# Sheet_1_2024-11-29.net
KiCad netlist of a schematic drawn in Altium Designer
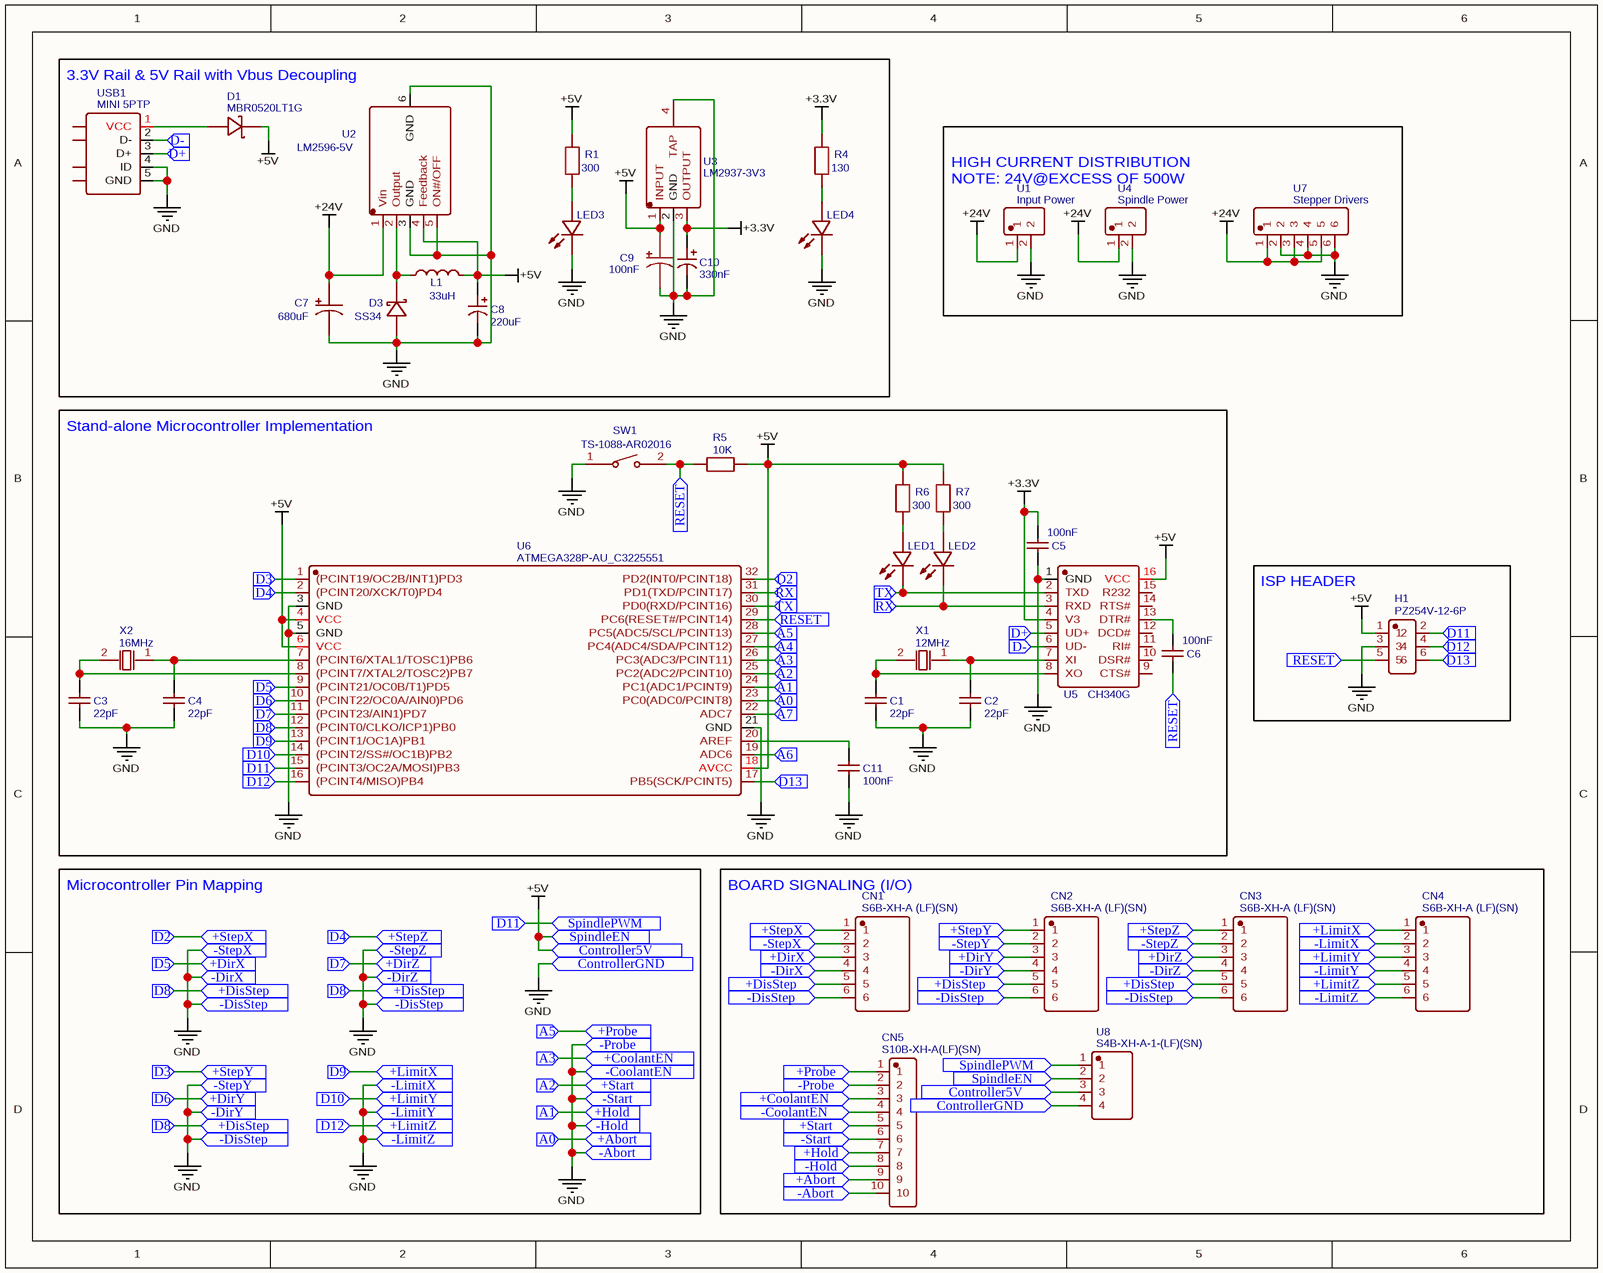
[diagram p0: Sheet_1_2024-11-29.schdoc]

(export (version "E")
  (design (tool "Eeschema 10.0.6"))
  (components
    (comp (ref "C1")
      (value "22pF")
      (fields (field (name "MANUFACTURER") "YAGEO(国巨)"))
      (libsource (lib "altium-import") (part "root_1_22pF_"))
    )
    (comp (ref "C2")
      (value "22pF")
      (fields (field (name "MANUFACTURER") "YAGEO(国巨)"))
      (libsource (lib "altium-import") (part "root_1_22pF_"))
    )
    (comp (ref "C3")
      (value "22pF")
      (fields (field (name "MANUFACTURER") "YAGEO(国巨)"))
      (libsource (lib "altium-import") (part "root_1_22pF_"))
    )
    (comp (ref "C4")
      (value "22pF")
      (fields (field (name "MANUFACTURER") "YAGEO(国巨)"))
      (libsource (lib "altium-import") (part "root_1_22pF_"))
    )
    (comp (ref "C5")
      (value "100nF")
      (fields (field (name "MANUFACTURER") "YAGEO(国巨)"))
      (libsource (lib "altium-import") (part "root_3_100nF_"))
    )
    (comp (ref "C6")
      (value "100nF")
      (fields (field (name "MANUFACTURER") "YAGEO(国巨)"))
      (libsource (lib "altium-import") (part "root_3_100nF_"))
    )
    (comp (ref "C7")
      (value "680uF")
      (fields (field (name "MANUFACTURER") "lelon(立隆)") (field (name "CONTRIBUTOR") "LCSC"))
      (libsource (lib "altium-import") (part "root_3_680uF_"))
    )
    (comp (ref "C8")
      (value "220uF")
      (fields (field (name "MANUFACTURER") "KNSCHA(科尼盛)") (field (name "CONTRIBUTOR") "lcsc"))
      (libsource (lib "altium-import") (part "root_3_220uF_"))
    )
    (comp (ref "C9")
      (value "100nF")
      (fields
        (field (name "MANUFACTURER") "HUAWEI(华威集团)")
        (field (name "MANUFACTURER PART") "VT1H0R1MB054000CE0")
        (field (name "CONTRIBUTOR") "LCSC")
      )
      (libsource (lib "altium-import") (part "root_0_100nF_"))
    )
    (comp (ref "C10")
      (value "330nF")
      (fields
        (field (name "MANUFACTURER") "ST(先科)")
        (field (name "MANUFACTURER PART") "CK1HR33MCRC54")
        (field (name "CONTRIBUTOR") "LCSC")
      )
      (libsource (lib "altium-import") (part "root_3_330nF_"))
    )
    (comp (ref "C11")
      (value "100nF")
      (fields (field (name "MANUFACTURER") "YAGEO(国巨)"))
      (libsource (lib "altium-import") (part "root_1_100nF_"))
    )
    (comp (ref "CN1")
      (value "S6B-XH-A (LF)(SN)")
      (fields (field (name "MANUFACTURER") "JST") (field (name "CONTRIBUTOR") "LCSC"))
      (libsource (lib "altium-import") (part "root_0_S6B-XH-A (LF)(SN)_"))
    )
    (comp (ref "CN2")
      (value "S6B-XH-A (LF)(SN)")
      (fields (field (name "MANUFACTURER") "JST") (field (name "CONTRIBUTOR") "LCSC"))
      (libsource (lib "altium-import") (part "root_0_S6B-XH-A (LF)(SN)_"))
    )
    (comp (ref "CN3")
      (value "S6B-XH-A (LF)(SN)")
      (fields (field (name "MANUFACTURER") "JST") (field (name "CONTRIBUTOR") "LCSC"))
      (libsource (lib "altium-import") (part "root_0_S6B-XH-A (LF)(SN)_"))
    )
    (comp (ref "CN4")
      (value "S6B-XH-A (LF)(SN)")
      (fields (field (name "MANUFACTURER") "JST") (field (name "CONTRIBUTOR") "LCSC"))
      (libsource (lib "altium-import") (part "root_0_S6B-XH-A (LF)(SN)_"))
    )
    (comp (ref "CN5")
      (value "S10B-XH-A(LF)(SN)")
      (fields (field (name "MANUFACTURER") "JST") (field (name "CONTRIBUTOR") "LCSC"))
      (libsource (lib "altium-import") (part "root_0_S10B-XH-A(LF)(SN)_"))
    )
    (comp (ref "D1")
      (value "MBR0520LT1G")
      (fields (field (name "MANUFACTURER") "onsemi(安森美)"))
      (libsource (lib "altium-import") (part "root_2_MBR0520LT1G_"))
    )
    (comp (ref "D3")
      (value "SS34")
      (fields (field (name "MANUFACTURER") "DOWO(东沃)") (field (name "CONTRIBUTOR") "lcsc"))
      (libsource (lib "altium-import") (part "root_3_SS34_"))
    )
    (comp (ref "H1")
      (value "PZ254V-12-6P")
      (fields (field (name "MANUFACTURER") "XFCN(兴飞)") (field (name "CONTRIBUTOR") "LCSC"))
      (libsource (lib "altium-import") (part "root_0_PZ254V-12-6P_"))
    )
    (comp (ref "L1")
      (value "33uH")
      (fields (field (name "MANUFACTURER") "GLE(格莱尔)") (field (name "CONTRIBUTOR") "lcsc"))
      (libsource (lib "altium-import") (part "root_0_33uH_"))
    )
    (comp (ref "LED1")
      (value "SZYY0603O")
      (fields (field (name "MANUFACTURER") "yongyu(永裕光电)") (field (name "CONTRIBUTOR") "LCSC"))
      (libsource (lib "altium-import") (part "root_1_SZYY0603O_"))
    )
    (comp (ref "LED2")
      (value "SZYY0603O")
      (fields (field (name "MANUFACTURER") "yongyu(永裕光电)") (field (name "CONTRIBUTOR") "LCSC"))
      (libsource (lib "altium-import") (part "root_1_SZYY0603O_"))
    )
    (comp (ref "LED3")
      (value "SZYY0603O")
      (fields (field (name "MANUFACTURER") "yongyu(永裕光电)") (field (name "CONTRIBUTOR") "LCSC"))
      (libsource (lib "altium-import") (part "root_1_SZYY0603O_"))
    )
    (comp (ref "LED4")
      (value "SZYY0603O")
      (fields (field (name "MANUFACTURER") "yongyu(永裕光电)") (field (name "CONTRIBUTOR") "LCSC"))
      (libsource (lib "altium-import") (part "root_1_SZYY0603O_"))
    )
    (comp (ref "R1")
      (value "300")
      (fields (field (name "MANUFACTURER") "Milliohm(毫欧)") (field (name "CONTRIBUTOR") "lcsc"))
      (libsource (lib "altium-import") (part "root_1_300_"))
    )
    (comp (ref "R4")
      (value "130")
      (fields (field (name "MANUFACTURER") "Milliohm(毫欧)") (field (name "CONTRIBUTOR") "lcsc"))
      (libsource (lib "altium-import") (part "root_1_130_"))
    )
    (comp (ref "R5")
      (value "10K")
      (fields (field (name "MANUFACTURER") "Milliohm(毫欧)") (field (name "CONTRIBUTOR") "lcsc"))
      (libsource (lib "altium-import") (part "root_2_10K_"))
    )
    (comp (ref "R6")
      (value "300")
      (fields (field (name "MANUFACTURER") "Milliohm(毫欧)") (field (name "CONTRIBUTOR") "lcsc"))
      (libsource (lib "altium-import") (part "root_1_300_"))
    )
    (comp (ref "R7")
      (value "300")
      (fields (field (name "MANUFACTURER") "Milliohm(毫欧)") (field (name "CONTRIBUTOR") "lcsc"))
      (libsource (lib "altium-import") (part "root_1_300_"))
    )
    (comp (ref "SW1")
      (value "TS-1088-AR02016")
      (fields (field (name "MANUFACTURER") "XUNPU(讯普)") (field (name "CONTRIBUTOR") "LCSC"))
      (libsource (lib "altium-import") (part "root_0_TS-1088-AR02016_"))
    )
    (comp (ref "U1")
      (value "Input Power")
      (fields (field (name "MANUFACTURER") "DORABO(地博电气)") (field (name "CONTRIBUTOR") "LCSC"))
      (libsource (lib "altium-import") (part "root_1_Input Power_"))
    )
    (comp (ref "U2")
      (value "LM2596-5V")
      (fields (field (name "MANUFACTURER") "MSKSEMI(美森科)") (field (name "CONTRIBUTOR") "lcsc"))
      (libsource (lib "altium-import") (part "root_1_LM2596-5V_"))
    )
    (comp (ref "U3")
      (value "LM2937-3V3")
      (fields (field (name "MANUFACTURER") "TI(德州仪器)") (field (name "CONTRIBUTOR") "LCSC"))
      (libsource (lib "altium-import") (part "root_0_LM2937-3V3_"))
    )
    (comp (ref "U4")
      (value "Spindle Power")
      (fields (field (name "MANUFACTURER") "DORABO(地博电气)") (field (name "CONTRIBUTOR") "LCSC"))
      (libsource (lib "altium-import") (part "root_1_Spindle Power_"))
    )
    (comp (ref "U5")
      (value "CH340G")
      (fields (field (name "MANUFACTURER") "WCH(南京沁恒)"))
      (libsource (lib "altium-import") (part "root_0_CH340G_"))
    )
    (comp (ref "U6")
      (value "ATMEGA328P-AU_C3225551")
      (fields (field (name "MANUFACTURER") "MICROCHIP(美国微芯)") (field (name "CONTRIBUTOR") "lcsc"))
      (libsource (lib "altium-import") (part "root_0_ATMEGA328P-AU_C3225551_"))
    )
    (comp (ref "U7")
      (value "Stepper Drivers")
      (fields (field (name "MANUFACTURER") "DORABO(地博电气)") (field (name "CONTRIBUTOR") "LCSC"))
      (libsource (lib "altium-import") (part "root_1_Stepper Drivers_"))
    )
    (comp (ref "U8")
      (value "S4B-XH-A-1-(LF)(SN)")
      (fields (field (name "MANUFACTURER") "JST") (field (name "CONTRIBUTOR") "LCSC"))
      (libsource (lib "altium-import") (part "root_0_S4B-XH-A-1-(LF)(SN)_"))
    )
    (comp (ref "USB1")
      (value "MINI 5PTP")
      (fields (field (name "MANUFACTURER") "SHOU HAN(首韩)") (field (name "CONTRIBUTOR") "LCSC"))
      (libsource (lib "altium-import") (part "root_0_MINI 5PTP_"))
    )
    (comp (ref "X1")
      (value "12MHz")
      (fields (field (name "MANUFACTURER") "ECS") (field (name "CONTRIBUTOR") "lcsc"))
      (libsource (lib "altium-import") (part "root_2_12MHz_"))
    )
    (comp (ref "X2")
      (value "16MHz")
      (fields (field (name "MANUFACTURER") "ECS") (field (name "CONTRIBUTOR") "lcsc"))
      (libsource (lib "altium-import") (part "root_2_16MHz_"))
    )
  )
  (nets
    (net (code "1") (name "+3.3V") (class "Default")
      (node (ref "C10") (pin "1") (pinfunction "1_1") (pintype "passive"))
      (node (ref "C5") (pin "1") (pinfunction "1_1") (pintype "passive"))
      (node (ref "R4") (pin "2") (pinfunction "2_2") (pintype "passive"))
      (node (ref "U3") (pin "3") (pinfunction "OUTPUT_3") (pintype "passive"))
      (node (ref "U5") (pin "4") (pinfunction "V3_4") (pintype "passive"))
    )
    (net (code "2") (name "+5V") (class "Default")
      (node (ref "C8") (pin "1") (pinfunction "1_1") (pintype "passive"))
      (node (ref "C9") (pin "1") (pinfunction "1_1") (pintype "passive"))
      (node (ref "D1") (pin "1") (pinfunction "C_1") (pintype "passive"))
      (node (ref "H1") (pin "1") (pinfunction "1_1") (pintype "passive"))
      (node (ref "L1") (pin "2") (pinfunction "2_2") (pintype "passive"))
      (node (ref "R1") (pin "2") (pinfunction "2_2") (pintype "passive"))
      (node (ref "R5") (pin "1") (pinfunction "1_1") (pintype "passive"))
      (node (ref "R6") (pin "2") (pinfunction "2_2") (pintype "passive"))
      (node (ref "R7") (pin "2") (pinfunction "2_2") (pintype "passive"))
      (node (ref "U2") (pin "4") (pinfunction "Feedback_4") (pintype "passive"))
      (node (ref "U3") (pin "1") (pinfunction "INPUT_1") (pintype "passive"))
      (node (ref "U5") (pin "16") (pinfunction "VCC_16") (pintype "passive"))
      (node (ref "U6") (pin "18") (pinfunction "AVCC_18") (pintype "passive"))
      (node (ref "U6") (pin "4") (pinfunction "VCC_4") (pintype "passive"))
      (node (ref "U6") (pin "6") (pinfunction "VCC_6") (pintype "passive"))
      (node (ref "U8") (pin "2") (pinfunction "2_2") (pintype "passive"))
      (node (ref "U8") (pin "3") (pinfunction "3_3") (pintype "passive"))
    )
    (net (code "3") (name "+24V") (class "Default")
      (node (ref "C7") (pin "1") (pinfunction "1_1") (pintype "passive"))
      (node (ref "U1") (pin "1") (pinfunction "1_1") (pintype "passive"))
      (node (ref "U2") (pin "1") (pinfunction "Vin_1") (pintype "passive"))
      (node (ref "U4") (pin "1") (pinfunction "1_1") (pintype "passive"))
      (node (ref "U7") (pin "1") (pinfunction "1_1") (pintype "passive"))
      (node (ref "U7") (pin "3") (pinfunction "3_3") (pintype "passive"))
      (node (ref "U7") (pin "5") (pinfunction "5_5") (pintype "passive"))
    )
    (net (code "4") (name "/+Abort") (class "Default")
      (node (ref "CN5") (pin "9") (pinfunction "9_9") (pintype "passive"))
      (node (ref "U6") (pin "23") (pinfunction "PC0(ADC0/PCINT8)_23") (pintype "passive"))
    )
    (net (code "5") (name "/+CoolantEN") (class "Default")
      (node (ref "CN5") (pin "3") (pinfunction "3_3") (pintype "passive"))
      (node (ref "U6") (pin "26") (pinfunction "PC3(ADC3/PCINT11)_26") (pintype "passive"))
    )
    (net (code "6") (name "/+DirX") (class "Default")
      (node (ref "CN1") (pin "3") (pinfunction "3_3") (pintype "passive"))
      (node (ref "U6") (pin "9") (pinfunction "(PCINT21/OC0B/T1)PD5_9") (pintype "passive"))
    )
    (net (code "7") (name "/+DirY") (class "Default")
      (node (ref "CN2") (pin "3") (pinfunction "3_3") (pintype "passive"))
      (node (ref "U6") (pin "10") (pinfunction "(PCINT22/OC0A/AIN0)PD6_10") (pintype "passive"))
    )
    (net (code "8") (name "/+DirZ") (class "Default")
      (node (ref "CN3") (pin "3") (pinfunction "3_3") (pintype "passive"))
      (node (ref "U6") (pin "11") (pinfunction "(PCINT23/AIN1)PD7_11") (pintype "passive"))
    )
    (net (code "9") (name "/+DisStep") (class "Default")
      (node (ref "CN1") (pin "5") (pinfunction "5_5") (pintype "passive"))
      (node (ref "CN2") (pin "5") (pinfunction "5_5") (pintype "passive"))
      (node (ref "CN3") (pin "5") (pinfunction "5_5") (pintype "passive"))
      (node (ref "U6") (pin "12") (pinfunction "(PCINT0/CLKO/ICP1)PB0_12") (pintype "passive"))
    )
    (net (code "10") (name "/+Hold") (class "Default")
      (node (ref "CN5") (pin "7") (pinfunction "7_7") (pintype "passive"))
      (node (ref "U6") (pin "24") (pinfunction "PC1(ADC1/PCINT9)_24") (pintype "passive"))
    )
    (net (code "11") (name "/+LimitX") (class "Default")
      (node (ref "CN4") (pin "1") (pinfunction "1_1") (pintype "passive"))
      (node (ref "U6") (pin "13") (pinfunction "(PCINT1/OC1A)PB1_13") (pintype "passive"))
    )
    (net (code "12") (name "/+LimitY") (class "Default")
      (node (ref "CN4") (pin "3") (pinfunction "3_3") (pintype "passive"))
      (node (ref "U6") (pin "14") (pinfunction "(PCINT2/SS#/OC1B)PB2_14") (pintype "passive"))
    )
    (net (code "13") (name "/+LimitZ") (class "Default")
      (node (ref "CN4") (pin "5") (pinfunction "5_5") (pintype "passive"))
      (node (ref "H1") (pin "4") (pinfunction "4_4") (pintype "passive"))
      (node (ref "U6") (pin "16") (pinfunction "(PCINT4/MISO)PB4_16") (pintype "passive"))
    )
    (net (code "14") (name "/+Probe") (class "Default")
      (node (ref "CN5") (pin "1") (pinfunction "1_1") (pintype "passive"))
      (node (ref "U6") (pin "28") (pinfunction "PC5(ADC5/SCL/PCINT13)_28") (pintype "passive"))
    )
    (net (code "15") (name "/+Start") (class "Default")
      (node (ref "CN5") (pin "5") (pinfunction "5_5") (pintype "passive"))
      (node (ref "U6") (pin "25") (pinfunction "PC2(ADC2/PCINT10)_25") (pintype "passive"))
    )
    (net (code "16") (name "/+StepX") (class "Default")
      (node (ref "CN1") (pin "1") (pinfunction "1_1") (pintype "passive"))
      (node (ref "U6") (pin "32") (pinfunction "PD2(INT0/PCINT18)_32") (pintype "passive"))
    )
    (net (code "17") (name "/+StepY") (class "Default")
      (node (ref "CN2") (pin "1") (pinfunction "1_1") (pintype "passive"))
      (node (ref "U6") (pin "1") (pinfunction "(PCINT19/OC2B/INT1)PD3_1") (pintype "passive"))
    )
    (net (code "18") (name "/+StepZ") (class "Default")
      (node (ref "CN3") (pin "1") (pinfunction "1_1") (pintype "passive"))
      (node (ref "U6") (pin "2") (pinfunction "(PCINT20/XCK/T0)PD4_2") (pintype "passive"))
    )
    (net (code "19") (name "/A4") (class "Default")
      (node (ref "U6") (pin "27") (pinfunction "PC4(ADC4/SDA/PCINT12)_27") (pintype "passive"))
    )
    (net (code "20") (name "/A6") (class "Default")
      (node (ref "U6") (pin "19") (pinfunction "ADC6_19") (pintype "passive"))
    )
    (net (code "21") (name "/A7") (class "Default")
      (node (ref "U6") (pin "22") (pinfunction "ADC7_22") (pintype "passive"))
    )
    (net (code "22") (name "/D+") (class "Default")
      (node (ref "U5") (pin "5") (pinfunction "UD+_5") (pintype "passive"))
      (node (ref "USB1") (pin "3") (pinfunction "D+_3") (pintype "passive"))
    )
    (net (code "23") (name "/D-") (class "Default")
      (node (ref "U5") (pin "6") (pinfunction "UD-_6") (pintype "passive"))
      (node (ref "USB1") (pin "2") (pinfunction "D-_2") (pintype "passive"))
    )
    (net (code "24") (name "/D11") (class "Default")
      (node (ref "H1") (pin "2") (pinfunction "2_2") (pintype "passive"))
      (node (ref "U6") (pin "15") (pinfunction "(PCINT3/OC2A/MOSI)PB3_15") (pintype "passive"))
      (node (ref "U8") (pin "1") (pinfunction "1_1") (pintype "passive"))
    )
    (net (code "25") (name "/D13") (class "Default")
      (node (ref "H1") (pin "6") (pinfunction "6_6") (pintype "passive"))
      (node (ref "U6") (pin "17") (pinfunction "PB5(SCK/PCINT5)_17") (pintype "passive"))
    )
    (net (code "26") (name "/RESET") (class "Default")
      (node (ref "C6") (pin "2") (pinfunction "2_2") (pintype "passive"))
      (node (ref "H1") (pin "5") (pinfunction "5_5") (pintype "passive"))
      (node (ref "R5") (pin "2") (pinfunction "2_2") (pintype "passive"))
      (node (ref "SW1") (pin "2") (pinfunction "2_2") (pintype "passive"))
      (node (ref "U6") (pin "29") (pinfunction "PC6(RESET#/PCINT14)_29") (pintype "passive"))
    )
    (net (code "27") (name "/RX") (class "Default")
      (node (ref "LED2") (pin "2") (pinfunction "-_2") (pintype "passive"))
      (node (ref "U5") (pin "3") (pinfunction "RXD_3") (pintype "passive"))
      (node (ref "U6") (pin "31") (pinfunction "PD1(TXD/PCINT17)_31") (pintype "passive"))
    )
    (net (code "28") (name "/TX") (class "Default")
      (node (ref "LED1") (pin "2") (pinfunction "-_2") (pintype "passive"))
      (node (ref "U5") (pin "2") (pinfunction "TXD_2") (pintype "passive"))
      (node (ref "U6") (pin "30") (pinfunction "PD0(RXD/PCINT16)_30") (pintype "passive"))
    )
    (net (code "29") (name "GND") (class "Default")
      (node (ref "C1") (pin "1") (pinfunction "1_1") (pintype "passive"))
      (node (ref "C10") (pin "2") (pinfunction "2_2") (pintype "passive"))
      (node (ref "C11") (pin "1") (pinfunction "1_1") (pintype "passive"))
      (node (ref "C2") (pin "1") (pinfunction "1_1") (pintype "passive"))
      (node (ref "C3") (pin "1") (pinfunction "1_1") (pintype "passive"))
      (node (ref "C4") (pin "1") (pinfunction "1_1") (pintype "passive"))
      (node (ref "C5") (pin "2") (pinfunction "2_2") (pintype "passive"))
      (node (ref "C7") (pin "2") (pinfunction "2_2") (pintype "passive"))
      (node (ref "C8") (pin "2") (pinfunction "2_2") (pintype "passive"))
      (node (ref "C9") (pin "2") (pinfunction "2_2") (pintype "passive"))
      (node (ref "CN1") (pin "2") (pinfunction "2_2") (pintype "passive"))
      (node (ref "CN1") (pin "4") (pinfunction "4_4") (pintype "passive"))
      (node (ref "CN1") (pin "6") (pinfunction "6_6") (pintype "passive"))
      (node (ref "CN2") (pin "2") (pinfunction "2_2") (pintype "passive"))
      (node (ref "CN2") (pin "4") (pinfunction "4_4") (pintype "passive"))
      (node (ref "CN2") (pin "6") (pinfunction "6_6") (pintype "passive"))
      (node (ref "CN3") (pin "2") (pinfunction "2_2") (pintype "passive"))
      (node (ref "CN3") (pin "4") (pinfunction "4_4") (pintype "passive"))
      (node (ref "CN3") (pin "6") (pinfunction "6_6") (pintype "passive"))
      (node (ref "CN4") (pin "2") (pinfunction "2_2") (pintype "passive"))
      (node (ref "CN4") (pin "4") (pinfunction "4_4") (pintype "passive"))
      (node (ref "CN4") (pin "6") (pinfunction "6_6") (pintype "passive"))
      (node (ref "CN5") (pin "10") (pinfunction "10_10") (pintype "passive"))
      (node (ref "CN5") (pin "2") (pinfunction "2_2") (pintype "passive"))
      (node (ref "CN5") (pin "4") (pinfunction "4_4") (pintype "passive"))
      (node (ref "CN5") (pin "6") (pinfunction "6_6") (pintype "passive"))
      (node (ref "CN5") (pin "8") (pinfunction "8_8") (pintype "passive"))
      (node (ref "D3") (pin "2") (pinfunction "A_2") (pintype "passive"))
      (node (ref "H1") (pin "3") (pinfunction "3_3") (pintype "passive"))
      (node (ref "LED3") (pin "2") (pinfunction "-_2") (pintype "passive"))
      (node (ref "LED4") (pin "2") (pinfunction "-_2") (pintype "passive"))
      (node (ref "SW1") (pin "1") (pinfunction "1_1") (pintype "passive"))
      (node (ref "U1") (pin "2") (pinfunction "2_2") (pintype "passive"))
      (node (ref "U2") (pin "3") (pinfunction "GND_3") (pintype "passive"))
      (node (ref "U2") (pin "5") (pinfunction "ON#/OFF_5") (pintype "passive"))
      (node (ref "U2") (pin "6") (pinfunction "GND_6") (pintype "passive"))
      (node (ref "U3") (pin "2") (pinfunction "GND_2") (pintype "passive"))
      (node (ref "U3") (pin "4") (pinfunction "TAP_4") (pintype "passive"))
      (node (ref "U4") (pin "2") (pinfunction "2_2") (pintype "passive"))
      (node (ref "U5") (pin "1") (pinfunction "GND_1") (pintype "passive"))
      (node (ref "U6") (pin "21") (pinfunction "GND_21") (pintype "passive"))
      (node (ref "U6") (pin "3") (pinfunction "GND_3") (pintype "passive"))
      (node (ref "U6") (pin "5") (pinfunction "GND_5") (pintype "passive"))
      (node (ref "U7") (pin "2") (pinfunction "2_2") (pintype "passive"))
      (node (ref "U7") (pin "4") (pinfunction "4_4") (pintype "passive"))
      (node (ref "U7") (pin "6") (pinfunction "6_6") (pintype "passive"))
      (node (ref "U8") (pin "4") (pinfunction "4_4") (pintype "passive"))
      (node (ref "USB1") (pin "4") (pinfunction "ID_4") (pintype "passive"))
      (node (ref "USB1") (pin "5") (pinfunction "GND_5") (pintype "passive"))
    )
    (net (code "30") (name "Net-(D1-A)") (class "Default")
      (node (ref "D1") (pin "2") (pinfunction "A_2") (pintype "passive"))
      (node (ref "USB1") (pin "1") (pinfunction "VCC_1") (pintype "passive"))
    )
    (net (code "31") (name "Net-(D3-K)") (class "Default")
      (node (ref "D3") (pin "1") (pinfunction "K_1") (pintype "passive"))
      (node (ref "L1") (pin "1") (pinfunction "1_1") (pintype "passive"))
      (node (ref "U2") (pin "2") (pinfunction "Output_2") (pintype "passive"))
    )
    (net (code "32") (name "Net-(LED1-+)") (class "Default")
      (node (ref "LED1") (pin "1") (pinfunction "+_1") (pintype "passive"))
      (node (ref "R6") (pin "1") (pinfunction "1_1") (pintype "passive"))
    )
    (net (code "33") (name "Net-(LED2-+)") (class "Default")
      (node (ref "LED2") (pin "1") (pinfunction "+_1") (pintype "passive"))
      (node (ref "R7") (pin "1") (pinfunction "1_1") (pintype "passive"))
    )
    (net (code "34") (name "Net-(LED3-+)") (class "Default")
      (node (ref "LED3") (pin "1") (pinfunction "+_1") (pintype "passive"))
      (node (ref "R1") (pin "1") (pinfunction "1_1") (pintype "passive"))
    )
    (net (code "35") (name "Net-(LED4-+)") (class "Default")
      (node (ref "LED4") (pin "1") (pinfunction "+_1") (pintype "passive"))
      (node (ref "R4") (pin "1") (pinfunction "1_1") (pintype "passive"))
    )
    (net (code "36") (name "Net-(U5-DTR#)") (class "Default")
      (node (ref "C6") (pin "1") (pinfunction "1_1") (pintype "passive"))
      (node (ref "U5") (pin "13") (pinfunction "DTR#_13") (pintype "passive"))
    )
    (net (code "37") (name "Net-(U5-XI)") (class "Default")
      (node (ref "C2") (pin "2") (pinfunction "2_2") (pintype "passive"))
      (node (ref "U5") (pin "7") (pinfunction "XI_7") (pintype "passive"))
      (node (ref "X1") (pin "1") (pinfunction "OSC1_1") (pintype "passive"))
    )
    (net (code "38") (name "Net-(U5-XO)") (class "Default")
      (node (ref "C1") (pin "2") (pinfunction "2_2") (pintype "passive"))
      (node (ref "U5") (pin "8") (pinfunction "XO_8") (pintype "passive"))
      (node (ref "X1") (pin "2") (pinfunction "OSC2_2") (pintype "passive"))
    )
    (net (code "39") (name "Net-(U6-(PCINT6{slash}XTAL1{slash}TOSC1)PB6)") (class "Default")
      (node (ref "C4") (pin "2") (pinfunction "2_2") (pintype "passive"))
      (node (ref "U6") (pin "7") (pinfunction "(PCINT6/XTAL1/TOSC1)PB6_7") (pintype "passive"))
      (node (ref "X2") (pin "1") (pinfunction "OSC1_1") (pintype "passive"))
    )
    (net (code "40") (name "Net-(U6-(PCINT7{slash}XTAL2{slash}TOSC2)PB7)") (class "Default")
      (node (ref "C3") (pin "2") (pinfunction "2_2") (pintype "passive"))
      (node (ref "U6") (pin "8") (pinfunction "(PCINT7/XTAL2/TOSC2)PB7_8") (pintype "passive"))
      (node (ref "X2") (pin "2") (pinfunction "OSC2_2") (pintype "passive"))
    )
    (net (code "41") (name "Net-(U6-AREF)") (class "Default")
      (node (ref "C11") (pin "2") (pinfunction "2_2") (pintype "passive"))
      (node (ref "U6") (pin "20") (pinfunction "AREF_20") (pintype "passive"))
    )
    (net (code "42") (name "unconnected-(U5-CTS#-Pad9)") (class "Default")
      (node (ref "U5") (pin "9") (pinfunction "CTS#_9") (pintype "passive"))
    )
    (net (code "43") (name "unconnected-(U5-DCD#-Pad12)") (class "Default")
      (node (ref "U5") (pin "12") (pinfunction "DCD#_12") (pintype "passive"))
    )
    (net (code "44") (name "unconnected-(U5-DSR#-Pad10)") (class "Default")
      (node (ref "U5") (pin "10") (pinfunction "DSR#_10") (pintype "passive"))
    )
    (net (code "45") (name "unconnected-(U5-R232-Pad15)") (class "Default")
      (node (ref "U5") (pin "15") (pinfunction "R232_15") (pintype "passive"))
    )
    (net (code "46") (name "unconnected-(U5-RI#-Pad11)") (class "Default")
      (node (ref "U5") (pin "11") (pinfunction "RI#_11") (pintype "passive"))
    )
    (net (code "47") (name "unconnected-(U5-RTS#-Pad14)") (class "Default")
      (node (ref "U5") (pin "14") (pinfunction "RTS#_14") (pintype "passive"))
    )
    (net (code "48") (name "unconnected-(USB1-EH-Pad6)") (class "Default")
      (node (ref "USB1") (pin "6") (pinfunction "EH_6") (pintype "passive"))
    )
    (net (code "49") (name "unconnected-(USB1-EH-Pad7)") (class "Default")
      (node (ref "USB1") (pin "7") (pinfunction "EH_7") (pintype "passive"))
    )
    (net (code "50") (name "unconnected-(USB1-EH-Pad8)") (class "Default")
      (node (ref "USB1") (pin "8") (pinfunction "EH_8") (pintype "passive"))
    )
    (net (code "51") (name "unconnected-(USB1-EH-Pad9)") (class "Default")
      (node (ref "USB1") (pin "9") (pinfunction "EH_9") (pintype "passive"))
    )
  )
)
